# schema-projet-elec.net
KiCad netlist of a schematic drawn in EAGLE
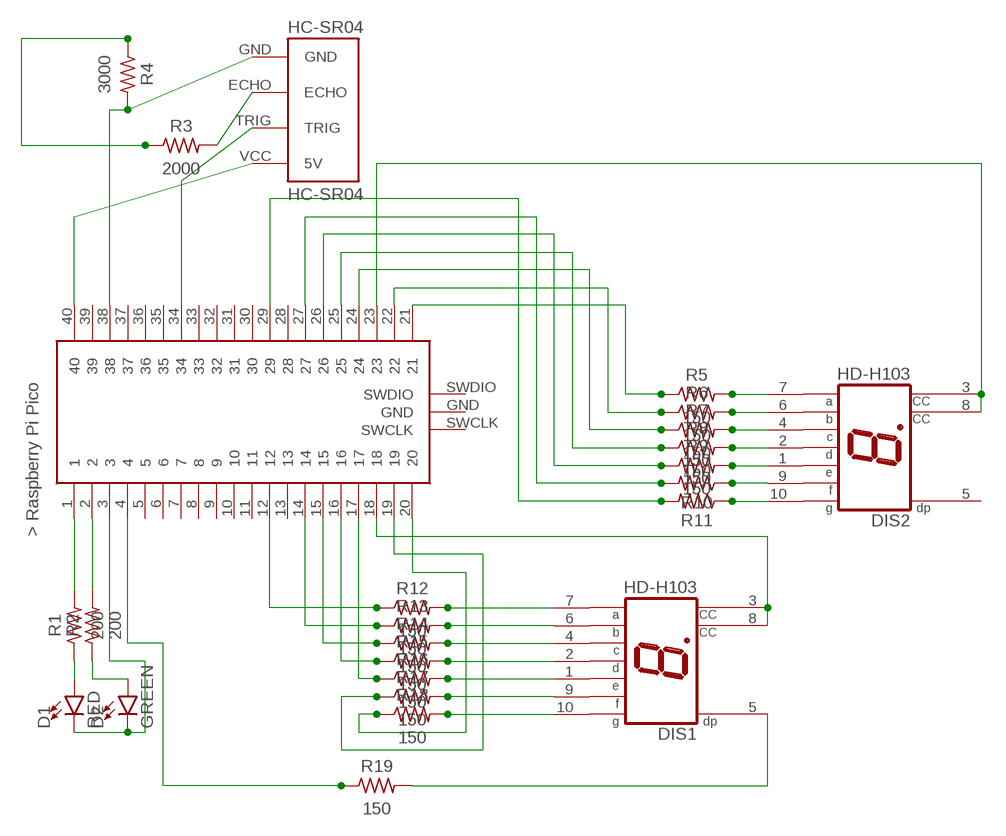
[diagram p0: schematic, sheet 1]

(export (version "E")
  (design (tool "Eeschema 10.0.6"))
  (components
    (comp (ref "D1")
      (value "RED")
      (footprint "eagle-import:LED-0603")
      (libsource (lib "eagle-import") (part "LED-RED0603"))
    )
    (comp (ref "D2")
      (value "GREEN")
      (footprint "eagle-import:LED-0603")
      (libsource (lib "eagle-import") (part "LED-GREEN0603"))
    )
    (comp (ref "DIS1")
      (value "HD-H103")
      (footprint "eagle-import:HDSP-M")
      (libsource (lib "eagle-import") (part "HD-H103"))
    )
    (comp (ref "DIS2")
      (value "HD-H103")
      (footprint "eagle-import:HDSP-M")
      (libsource (lib "eagle-import") (part "HD-H103"))
    )
    (comp (ref "HC-SR04")
      (value "HC-SR04")
      (footprint "eagle-import:HC-SR04_FOOTPRINT")
      (libsource (lib "eagle-import") (part "HC-SR04"))
    )
    (comp (ref "R1")
      (value "200")
      (footprint "eagle-import:RESAD724W46L381D178B")
      (libsource (lib "eagle-import") (part "R-USAXIAL-7.2MM-PITCH_"))
    )
    (comp (ref "R2")
      (value "200")
      (footprint "eagle-import:RESAD724W46L381D178B")
      (libsource (lib "eagle-import") (part "R-USAXIAL-7.2MM-PITCH_"))
    )
    (comp (ref "R3")
      (value "2000")
      (footprint "eagle-import:RESAD724W46L381D178B")
      (libsource (lib "eagle-import") (part "R-USAXIAL-7.2MM-PITCH_"))
    )
    (comp (ref "R4")
      (value "3000")
      (footprint "eagle-import:RESAD724W46L381D178B")
      (libsource (lib "eagle-import") (part "R-USAXIAL-7.2MM-PITCH_"))
    )
    (comp (ref "R5")
      (value "150")
      (footprint "eagle-import:RESAD724W46L381D178B")
      (libsource (lib "eagle-import") (part "R-USAXIAL-7.2MM-PITCH_"))
    )
    (comp (ref "R6")
      (value "150")
      (footprint "eagle-import:RESAD724W46L381D178B")
      (libsource (lib "eagle-import") (part "R-USAXIAL-7.2MM-PITCH_"))
    )
    (comp (ref "R7")
      (value "150")
      (footprint "eagle-import:RESAD724W46L381D178B")
      (libsource (lib "eagle-import") (part "R-USAXIAL-7.2MM-PITCH_"))
    )
    (comp (ref "R8")
      (value "150")
      (footprint "eagle-import:RESAD724W46L381D178B")
      (libsource (lib "eagle-import") (part "R-USAXIAL-7.2MM-PITCH_"))
    )
    (comp (ref "R9")
      (value "150")
      (footprint "eagle-import:RESAD724W46L381D178B")
      (libsource (lib "eagle-import") (part "R-USAXIAL-7.2MM-PITCH_"))
    )
    (comp (ref "R10")
      (value "150")
      (footprint "eagle-import:RESAD724W46L381D178B")
      (libsource (lib "eagle-import") (part "R-USAXIAL-7.2MM-PITCH_"))
    )
    (comp (ref "R11")
      (value "150")
      (footprint "eagle-import:RESAD724W46L381D178B")
      (libsource (lib "eagle-import") (part "R-USAXIAL-7.2MM-PITCH_"))
    )
    (comp (ref "R12")
      (value "150")
      (footprint "eagle-import:RESAD724W46L381D178B")
      (libsource (lib "eagle-import") (part "R-USAXIAL-7.2MM-PITCH_"))
    )
    (comp (ref "R13")
      (value "150")
      (footprint "eagle-import:RESAD724W46L381D178B")
      (libsource (lib "eagle-import") (part "R-USAXIAL-7.2MM-PITCH_"))
    )
    (comp (ref "R14")
      (value "150")
      (footprint "eagle-import:RESAD724W46L381D178B")
      (libsource (lib "eagle-import") (part "R-USAXIAL-7.2MM-PITCH_"))
    )
    (comp (ref "R15")
      (value "150")
      (footprint "eagle-import:RESAD724W46L381D178B")
      (libsource (lib "eagle-import") (part "R-USAXIAL-7.2MM-PITCH_"))
    )
    (comp (ref "R16")
      (value "150")
      (footprint "eagle-import:RESAD724W46L381D178B")
      (libsource (lib "eagle-import") (part "R-USAXIAL-7.2MM-PITCH_"))
    )
    (comp (ref "R17")
      (value "150")
      (footprint "eagle-import:RESAD724W46L381D178B")
      (libsource (lib "eagle-import") (part "R-USAXIAL-7.2MM-PITCH_"))
    )
    (comp (ref "R18")
      (value "150")
      (footprint "eagle-import:RESAD724W46L381D178B")
      (libsource (lib "eagle-import") (part "R-USAXIAL-7.2MM-PITCH_"))
    )
    (comp (ref "R19")
      (value "150")
      (footprint "eagle-import:RESAD724W46L381D178B")
      (libsource (lib "eagle-import") (part "R-USAXIAL-7.2MM-PITCH_"))
    )
    (comp (ref "U$1")
      (value "RASPBERRY-PI-PICO_TH")
      (footprint "eagle-import:FT_RASPBERRY-PI-PICO_TH")
      (libsource (lib "eagle-import") (part "RASPBERRY-PI-PICO_TH"))
    )
  )
  (nets
    (net (code "1") (name "Net-(D1-PadA)") (class "Default")
      (node (ref "D1") (pin "A") (pinfunction "A_A") (pintype "passive"))
      (node (ref "R1") (pin "1") (pinfunction "1_1") (pintype "passive"))
    )
    (net (code "2") (name "Net-(D1-PadC)") (class "Default")
      (node (ref "D1") (pin "C") (pinfunction "C_C") (pintype "passive"))
      (node (ref "D2") (pin "C") (pinfunction "C_C") (pintype "passive"))
      (node (ref "U$1") (pin "3") (pinfunction "3_3") (pintype "bidirectional"))
    )
    (net (code "3") (name "Net-(D2-PadA)") (class "Default")
      (node (ref "D2") (pin "A") (pinfunction "A_A") (pintype "passive"))
      (node (ref "R2") (pin "1") (pinfunction "1_1") (pintype "passive"))
    )
    (net (code "4") (name "Net-(DIS1-A)") (class "Default")
      (node (ref "DIS1") (pin "7") (pinfunction "A_7") (pintype "passive"))
      (node (ref "R12") (pin "2") (pinfunction "2_2") (pintype "passive"))
    )
    (net (code "5") (name "Net-(DIS1-B)") (class "Default")
      (node (ref "DIS1") (pin "6") (pinfunction "B_6") (pintype "passive"))
      (node (ref "R13") (pin "2") (pinfunction "2_2") (pintype "passive"))
    )
    (net (code "6") (name "Net-(DIS1-C)") (class "Default")
      (node (ref "DIS1") (pin "4") (pinfunction "C_4") (pintype "passive"))
      (node (ref "R14") (pin "2") (pinfunction "2_2") (pintype "passive"))
    )
    (net (code "7") (name "Net-(DIS1-CC-Pad3)") (class "Default")
      (node (ref "DIS1") (pin "3") (pinfunction "CC_3") (pintype "passive"))
      (node (ref "DIS1") (pin "8") (pinfunction "CC_8") (pintype "passive"))
      (node (ref "U$1") (pin "18") (pinfunction "18_18") (pintype "bidirectional"))
    )
    (net (code "8") (name "Net-(DIS1-D)") (class "Default")
      (node (ref "DIS1") (pin "2") (pinfunction "D_2") (pintype "passive"))
      (node (ref "R15") (pin "2") (pinfunction "2_2") (pintype "passive"))
    )
    (net (code "9") (name "Net-(DIS1-DP)") (class "Default")
      (node (ref "DIS1") (pin "5") (pinfunction "DP_5") (pintype "passive"))
      (node (ref "R19") (pin "2") (pinfunction "2_2") (pintype "passive"))
    )
    (net (code "10") (name "Net-(DIS1-E)") (class "Default")
      (node (ref "DIS1") (pin "1") (pinfunction "E_1") (pintype "passive"))
      (node (ref "R16") (pin "2") (pinfunction "2_2") (pintype "passive"))
    )
    (net (code "11") (name "Net-(DIS1-F)") (class "Default")
      (node (ref "DIS1") (pin "9") (pinfunction "F_9") (pintype "passive"))
      (node (ref "R17") (pin "2") (pinfunction "2_2") (pintype "passive"))
    )
    (net (code "12") (name "Net-(DIS1-G)") (class "Default")
      (node (ref "DIS1") (pin "10") (pinfunction "G_10") (pintype "passive"))
      (node (ref "R18") (pin "2") (pinfunction "2_2") (pintype "passive"))
    )
    (net (code "13") (name "Net-(DIS2-A)") (class "Default")
      (node (ref "DIS2") (pin "7") (pinfunction "A_7") (pintype "passive"))
      (node (ref "R5") (pin "2") (pinfunction "2_2") (pintype "passive"))
    )
    (net (code "14") (name "Net-(DIS2-B)") (class "Default")
      (node (ref "DIS2") (pin "6") (pinfunction "B_6") (pintype "passive"))
      (node (ref "R6") (pin "2") (pinfunction "2_2") (pintype "passive"))
    )
    (net (code "15") (name "Net-(DIS2-C)") (class "Default")
      (node (ref "DIS2") (pin "4") (pinfunction "C_4") (pintype "passive"))
      (node (ref "R7") (pin "2") (pinfunction "2_2") (pintype "passive"))
    )
    (net (code "16") (name "Net-(DIS2-CC-Pad3)") (class "Default")
      (node (ref "DIS2") (pin "3") (pinfunction "CC_3") (pintype "passive"))
      (node (ref "DIS2") (pin "8") (pinfunction "CC_8") (pintype "passive"))
      (node (ref "U$1") (pin "23") (pinfunction "23_23") (pintype "bidirectional"))
    )
    (net (code "17") (name "Net-(DIS2-D)") (class "Default")
      (node (ref "DIS2") (pin "2") (pinfunction "D_2") (pintype "passive"))
      (node (ref "R8") (pin "2") (pinfunction "2_2") (pintype "passive"))
    )
    (net (code "18") (name "Net-(DIS2-E)") (class "Default")
      (node (ref "DIS2") (pin "1") (pinfunction "E_1") (pintype "passive"))
      (node (ref "R9") (pin "2") (pinfunction "2_2") (pintype "passive"))
    )
    (net (code "19") (name "Net-(DIS2-F)") (class "Default")
      (node (ref "DIS2") (pin "9") (pinfunction "F_9") (pintype "passive"))
      (node (ref "R10") (pin "1") (pinfunction "1_1") (pintype "passive"))
    )
    (net (code "20") (name "Net-(DIS2-G)") (class "Default")
      (node (ref "DIS2") (pin "10") (pinfunction "G_10") (pintype "passive"))
      (node (ref "R11") (pin "1") (pinfunction "1_1") (pintype "passive"))
    )
    (net (code "21") (name "Net-(HC-SR04-5V)") (class "Default")
      (node (ref "HC-SR04") (pin "VCC") (pinfunction "5V_VCC") (pintype "bidirectional"))
      (node (ref "U$1") (pin "40") (pinfunction "40_40") (pintype "bidirectional"))
    )
    (net (code "22") (name "Net-(HC-SR04-PadECHO)") (class "Default")
      (node (ref "HC-SR04") (pin "ECHO") (pinfunction "ECHO_ECHO") (pintype "bidirectional"))
      (node (ref "R3") (pin "2") (pinfunction "2_2") (pintype "passive"))
    )
    (net (code "23") (name "Net-(HC-SR04-PadGND)") (class "Default")
      (node (ref "HC-SR04") (pin "GND") (pinfunction "GND_GND") (pintype "bidirectional"))
      (node (ref "R4") (pin "2") (pinfunction "2_2") (pintype "passive"))
      (node (ref "U$1") (pin "38") (pinfunction "38_38") (pintype "bidirectional"))
    )
    (net (code "24") (name "Net-(HC-SR04-PadTRIG)") (class "Default")
      (node (ref "HC-SR04") (pin "TRIG") (pinfunction "TRIG_TRIG") (pintype "bidirectional"))
      (node (ref "U$1") (pin "34") (pinfunction "34_34") (pintype "bidirectional"))
    )
    (net (code "25") (name "Net-(R1-Pad2)") (class "Default")
      (node (ref "R1") (pin "2") (pinfunction "2_2") (pintype "passive"))
      (node (ref "U$1") (pin "1") (pinfunction "1_1") (pintype "bidirectional"))
    )
    (net (code "26") (name "Net-(R2-Pad2)") (class "Default")
      (node (ref "R2") (pin "2") (pinfunction "2_2") (pintype "passive"))
      (node (ref "U$1") (pin "2") (pinfunction "2_2") (pintype "bidirectional"))
    )
    (net (code "27") (name "Net-(R3-Pad1)") (class "Default")
      (node (ref "R3") (pin "1") (pinfunction "1_1") (pintype "passive"))
      (node (ref "R4") (pin "1") (pinfunction "1_1") (pintype "passive"))
    )
    (net (code "28") (name "Net-(R5-Pad1)") (class "Default")
      (node (ref "R5") (pin "1") (pinfunction "1_1") (pintype "passive"))
      (node (ref "U$1") (pin "21") (pinfunction "21_21") (pintype "bidirectional"))
    )
    (net (code "29") (name "Net-(R6-Pad1)") (class "Default")
      (node (ref "R6") (pin "1") (pinfunction "1_1") (pintype "passive"))
      (node (ref "U$1") (pin "22") (pinfunction "22_22") (pintype "bidirectional"))
    )
    (net (code "30") (name "Net-(R7-Pad1)") (class "Default")
      (node (ref "R7") (pin "1") (pinfunction "1_1") (pintype "passive"))
      (node (ref "U$1") (pin "24") (pinfunction "24_24") (pintype "bidirectional"))
    )
    (net (code "31") (name "Net-(R8-Pad1)") (class "Default")
      (node (ref "R8") (pin "1") (pinfunction "1_1") (pintype "passive"))
      (node (ref "U$1") (pin "25") (pinfunction "25_25") (pintype "bidirectional"))
    )
    (net (code "32") (name "Net-(R9-Pad1)") (class "Default")
      (node (ref "R9") (pin "1") (pinfunction "1_1") (pintype "passive"))
      (node (ref "U$1") (pin "26") (pinfunction "26_26") (pintype "bidirectional"))
    )
    (net (code "33") (name "Net-(R10-Pad2)") (class "Default")
      (node (ref "R10") (pin "2") (pinfunction "2_2") (pintype "passive"))
      (node (ref "U$1") (pin "27") (pinfunction "27_27") (pintype "bidirectional"))
    )
    (net (code "34") (name "Net-(R11-Pad2)") (class "Default")
      (node (ref "R11") (pin "2") (pinfunction "2_2") (pintype "passive"))
      (node (ref "U$1") (pin "29") (pinfunction "29_29") (pintype "bidirectional"))
    )
    (net (code "35") (name "Net-(R12-Pad1)") (class "Default")
      (node (ref "R12") (pin "1") (pinfunction "1_1") (pintype "passive"))
      (node (ref "U$1") (pin "12") (pinfunction "12_12") (pintype "bidirectional"))
    )
    (net (code "36") (name "Net-(R13-Pad1)") (class "Default")
      (node (ref "R13") (pin "1") (pinfunction "1_1") (pintype "passive"))
      (node (ref "U$1") (pin "14") (pinfunction "14_14") (pintype "bidirectional"))
    )
    (net (code "37") (name "Net-(R14-Pad1)") (class "Default")
      (node (ref "R14") (pin "1") (pinfunction "1_1") (pintype "passive"))
      (node (ref "U$1") (pin "15") (pinfunction "15_15") (pintype "bidirectional"))
    )
    (net (code "38") (name "Net-(R15-Pad1)") (class "Default")
      (node (ref "R15") (pin "1") (pinfunction "1_1") (pintype "passive"))
      (node (ref "U$1") (pin "16") (pinfunction "16_16") (pintype "bidirectional"))
    )
    (net (code "39") (name "Net-(R16-Pad1)") (class "Default")
      (node (ref "R16") (pin "1") (pinfunction "1_1") (pintype "passive"))
      (node (ref "U$1") (pin "17") (pinfunction "17_17") (pintype "bidirectional"))
    )
    (net (code "40") (name "Net-(R17-Pad1)") (class "Default")
      (node (ref "R17") (pin "1") (pinfunction "1_1") (pintype "passive"))
      (node (ref "U$1") (pin "19") (pinfunction "19_19") (pintype "bidirectional"))
    )
    (net (code "41") (name "Net-(R18-Pad1)") (class "Default")
      (node (ref "R18") (pin "1") (pinfunction "1_1") (pintype "passive"))
      (node (ref "U$1") (pin "20") (pinfunction "20_20") (pintype "bidirectional"))
    )
    (net (code "42") (name "Net-(R19-Pad1)") (class "Default")
      (node (ref "R19") (pin "1") (pinfunction "1_1") (pintype "passive"))
      (node (ref "U$1") (pin "4") (pinfunction "4_4") (pintype "bidirectional"))
    )
    (net (code "43") (name "unconnected-(DIS2-DP-Pad5)") (class "Default")
      (node (ref "DIS2") (pin "5") (pinfunction "DP_5") (pintype "passive"))
    )
    (net (code "44") (name "unconnected-(U$1-Pad5)") (class "Default")
      (node (ref "U$1") (pin "5") (pinfunction "5_5") (pintype "bidirectional"))
    )
    (net (code "45") (name "unconnected-(U$1-Pad6)") (class "Default")
      (node (ref "U$1") (pin "6") (pinfunction "6_6") (pintype "bidirectional"))
    )
    (net (code "46") (name "unconnected-(U$1-Pad7)") (class "Default")
      (node (ref "U$1") (pin "7") (pinfunction "7_7") (pintype "bidirectional"))
    )
    (net (code "47") (name "unconnected-(U$1-Pad8)") (class "Default")
      (node (ref "U$1") (pin "8") (pinfunction "8_8") (pintype "bidirectional"))
    )
    (net (code "48") (name "unconnected-(U$1-Pad9)") (class "Default")
      (node (ref "U$1") (pin "9") (pinfunction "9_9") (pintype "bidirectional"))
    )
    (net (code "49") (name "unconnected-(U$1-Pad10)") (class "Default")
      (node (ref "U$1") (pin "10") (pinfunction "10_10") (pintype "bidirectional"))
    )
    (net (code "50") (name "unconnected-(U$1-Pad11)") (class "Default")
      (node (ref "U$1") (pin "11") (pinfunction "11_11") (pintype "bidirectional"))
    )
    (net (code "51") (name "unconnected-(U$1-Pad13)") (class "Default")
      (node (ref "U$1") (pin "13") (pinfunction "13_13") (pintype "bidirectional"))
    )
    (net (code "52") (name "unconnected-(U$1-Pad28)") (class "Default")
      (node (ref "U$1") (pin "28") (pinfunction "28_28") (pintype "bidirectional"))
    )
    (net (code "53") (name "unconnected-(U$1-Pad30)") (class "Default")
      (node (ref "U$1") (pin "30") (pinfunction "30_30") (pintype "bidirectional"))
    )
    (net (code "54") (name "unconnected-(U$1-Pad31)") (class "Default")
      (node (ref "U$1") (pin "31") (pinfunction "31_31") (pintype "bidirectional"))
    )
    (net (code "55") (name "unconnected-(U$1-Pad32)") (class "Default")
      (node (ref "U$1") (pin "32") (pinfunction "32_32") (pintype "bidirectional"))
    )
    (net (code "56") (name "unconnected-(U$1-Pad33)") (class "Default")
      (node (ref "U$1") (pin "33") (pinfunction "33_33") (pintype "bidirectional"))
    )
    (net (code "57") (name "unconnected-(U$1-Pad35)") (class "Default")
      (node (ref "U$1") (pin "35") (pinfunction "35_35") (pintype "bidirectional"))
    )
    (net (code "58") (name "unconnected-(U$1-Pad36)") (class "Default")
      (node (ref "U$1") (pin "36") (pinfunction "36_36") (pintype "bidirectional"))
    )
    (net (code "59") (name "unconnected-(U$1-Pad37)") (class "Default")
      (node (ref "U$1") (pin "37") (pinfunction "37_37") (pintype "bidirectional"))
    )
    (net (code "60") (name "unconnected-(U$1-Pad39)") (class "Default")
      (node (ref "U$1") (pin "39") (pinfunction "39_39") (pintype "bidirectional"))
    )
    (net (code "61") (name "unconnected-(U$1-PadGND)") (class "Default")
      (node (ref "U$1") (pin "GND") (pinfunction "GND_GND") (pintype "bidirectional"))
    )
    (net (code "62") (name "unconnected-(U$1-PadSWCLK)") (class "Default")
      (node (ref "U$1") (pin "SWCLK") (pinfunction "SWCLK_SWCLK") (pintype "bidirectional"))
    )
    (net (code "63") (name "unconnected-(U$1-PadSWDIO)") (class "Default")
      (node (ref "U$1") (pin "SWDIO") (pinfunction "SWDIO_SWDIO") (pintype "bidirectional"))
    )
  )
)
